# LPCB221_-_LIMIT_SWITCHES.net
KiCad netlist of a schematic drawn in Altium Designer
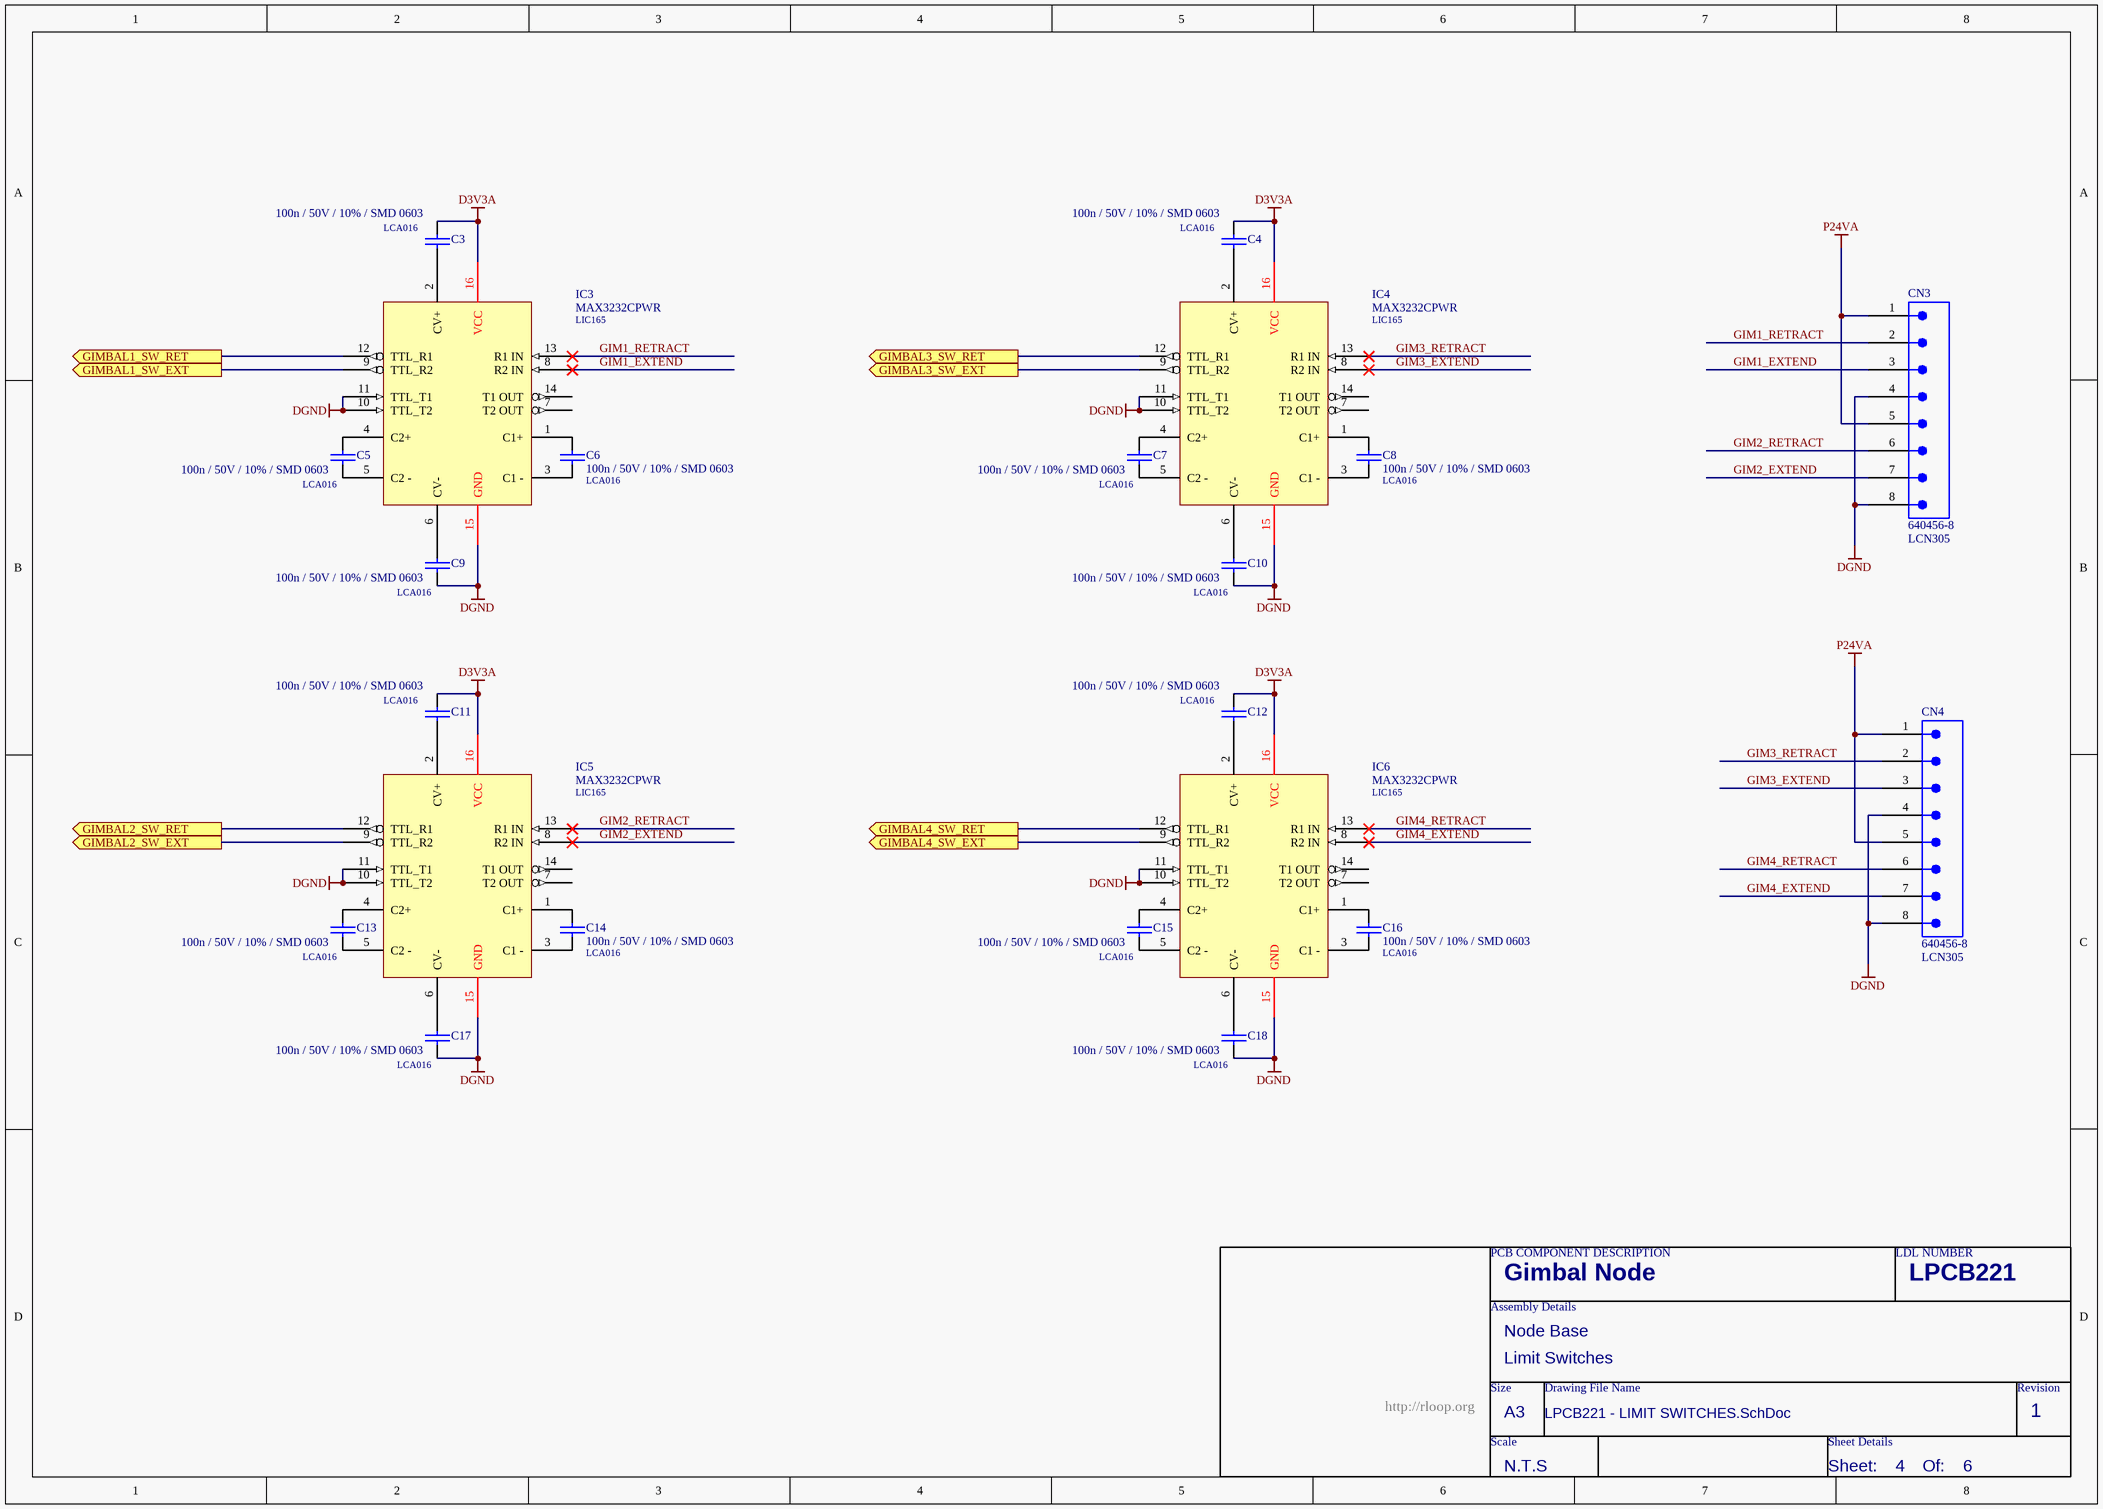
[diagram p0: LPCB221 - LIMIT SWITCHES.SchDoc]

(export (version "E")
  (design (tool "Eeschema 10.0.6"))
  (components
    (comp (ref "C3")
      (value "100n / 50V / 10% / SMD 0603")
      (footprint "LFP011__CC1608-0603-IPC7351_B")
      (description "Capacitor, Ceramic Chip, 100nF (0.1uF), 50V, 5%, SMD 0603 [LCA016]")
      (fields (field (name "LDL_NUMBER") "LCA016"))
      (libsource (lib "LDL_Capacitors") (part "100n / 50V / 10% / SMD 0603"))
    )
    (comp (ref "C4")
      (value "100n / 50V / 10% / SMD 0603")
      (footprint "LFP011__CC1608-0603-IPC7351_B")
      (description "Capacitor, Ceramic Chip, 100nF (0.1uF), 50V, 5%, SMD 0603 [LCA016]")
      (fields (field (name "LDL_NUMBER") "LCA016"))
      (libsource (lib "LDL_Capacitors") (part "100n / 50V / 10% / SMD 0603"))
    )
    (comp (ref "C5")
      (value "100n / 50V / 10% / SMD 0603")
      (footprint "LFP011__CC1608-0603-IPC7351_B")
      (description "Capacitor, Ceramic Chip, 100nF (0.1uF), 50V, 5%, SMD 0603 [LCA016]")
      (fields (field (name "LDL_NUMBER") "LCA016"))
      (libsource (lib "LDL_Capacitors") (part "100n / 50V / 10% / SMD 0603"))
    )
    (comp (ref "C6")
      (value "100n / 50V / 10% / SMD 0603")
      (footprint "LFP011__CC1608-0603-IPC7351_B")
      (description "Capacitor, Ceramic Chip, 100nF (0.1uF), 50V, 5%, SMD 0603 [LCA016]")
      (fields (field (name "LDL_NUMBER") "LCA016"))
      (libsource (lib "LDL_Capacitors") (part "100n / 50V / 10% / SMD 0603"))
    )
    (comp (ref "C7")
      (value "100n / 50V / 10% / SMD 0603")
      (footprint "LFP011__CC1608-0603-IPC7351_B")
      (description "Capacitor, Ceramic Chip, 100nF (0.1uF), 50V, 5%, SMD 0603 [LCA016]")
      (fields (field (name "LDL_NUMBER") "LCA016"))
      (libsource (lib "LDL_Capacitors") (part "100n / 50V / 10% / SMD 0603"))
    )
    (comp (ref "C8")
      (value "100n / 50V / 10% / SMD 0603")
      (footprint "LFP011__CC1608-0603-IPC7351_B")
      (description "Capacitor, Ceramic Chip, 100nF (0.1uF), 50V, 5%, SMD 0603 [LCA016]")
      (fields (field (name "LDL_NUMBER") "LCA016"))
      (libsource (lib "LDL_Capacitors") (part "100n / 50V / 10% / SMD 0603"))
    )
    (comp (ref "C9")
      (value "100n / 50V / 10% / SMD 0603")
      (footprint "LFP011__CC1608-0603-IPC7351_B")
      (description "Capacitor, Ceramic Chip, 100nF (0.1uF), 50V, 5%, SMD 0603 [LCA016]")
      (fields (field (name "LDL_NUMBER") "LCA016"))
      (libsource (lib "LDL_Capacitors") (part "100n / 50V / 10% / SMD 0603"))
    )
    (comp (ref "C10")
      (value "100n / 50V / 10% / SMD 0603")
      (footprint "LFP011__CC1608-0603-IPC7351_B")
      (description "Capacitor, Ceramic Chip, 100nF (0.1uF), 50V, 5%, SMD 0603 [LCA016]")
      (fields (field (name "LDL_NUMBER") "LCA016"))
      (libsource (lib "LDL_Capacitors") (part "100n / 50V / 10% / SMD 0603"))
    )
    (comp (ref "C11")
      (value "100n / 50V / 10% / SMD 0603")
      (footprint "LFP011__CC1608-0603-IPC7351_B")
      (description "Capacitor, Ceramic Chip, 100nF (0.1uF), 50V, 5%, SMD 0603 [LCA016]")
      (fields (field (name "LDL_NUMBER") "LCA016"))
      (libsource (lib "LDL_Capacitors") (part "100n / 50V / 10% / SMD 0603"))
    )
    (comp (ref "C12")
      (value "100n / 50V / 10% / SMD 0603")
      (footprint "LFP011__CC1608-0603-IPC7351_B")
      (description "Capacitor, Ceramic Chip, 100nF (0.1uF), 50V, 5%, SMD 0603 [LCA016]")
      (fields (field (name "LDL_NUMBER") "LCA016"))
      (libsource (lib "LDL_Capacitors") (part "100n / 50V / 10% / SMD 0603"))
    )
    (comp (ref "C13")
      (value "100n / 50V / 10% / SMD 0603")
      (footprint "LFP011__CC1608-0603-IPC7351_B")
      (description "Capacitor, Ceramic Chip, 100nF (0.1uF), 50V, 5%, SMD 0603 [LCA016]")
      (fields (field (name "LDL_NUMBER") "LCA016"))
      (libsource (lib "LDL_Capacitors") (part "100n / 50V / 10% / SMD 0603"))
    )
    (comp (ref "C14")
      (value "100n / 50V / 10% / SMD 0603")
      (footprint "LFP011__CC1608-0603-IPC7351_B")
      (description "Capacitor, Ceramic Chip, 100nF (0.1uF), 50V, 5%, SMD 0603 [LCA016]")
      (fields (field (name "LDL_NUMBER") "LCA016"))
      (libsource (lib "LDL_Capacitors") (part "100n / 50V / 10% / SMD 0603"))
    )
    (comp (ref "C15")
      (value "100n / 50V / 10% / SMD 0603")
      (footprint "LFP011__CC1608-0603-IPC7351_B")
      (description "Capacitor, Ceramic Chip, 100nF (0.1uF), 50V, 5%, SMD 0603 [LCA016]")
      (fields (field (name "LDL_NUMBER") "LCA016"))
      (libsource (lib "LDL_Capacitors") (part "100n / 50V / 10% / SMD 0603"))
    )
    (comp (ref "C16")
      (value "100n / 50V / 10% / SMD 0603")
      (footprint "LFP011__CC1608-0603-IPC7351_B")
      (description "Capacitor, Ceramic Chip, 100nF (0.1uF), 50V, 5%, SMD 0603 [LCA016]")
      (fields (field (name "LDL_NUMBER") "LCA016"))
      (libsource (lib "LDL_Capacitors") (part "100n / 50V / 10% / SMD 0603"))
    )
    (comp (ref "C17")
      (value "100n / 50V / 10% / SMD 0603")
      (footprint "LFP011__CC1608-0603-IPC7351_B")
      (description "Capacitor, Ceramic Chip, 100nF (0.1uF), 50V, 5%, SMD 0603 [LCA016]")
      (fields (field (name "LDL_NUMBER") "LCA016"))
      (libsource (lib "LDL_Capacitors") (part "100n / 50V / 10% / SMD 0603"))
    )
    (comp (ref "C18")
      (value "100n / 50V / 10% / SMD 0603")
      (footprint "LFP011__CC1608-0603-IPC7351_B")
      (description "Capacitor, Ceramic Chip, 100nF (0.1uF), 50V, 5%, SMD 0603 [LCA016]")
      (fields (field (name "LDL_NUMBER") "LCA016"))
      (libsource (lib "LDL_Capacitors") (part "100n / 50V / 10% / SMD 0603"))
    )
    (comp (ref "CN3")
      (value "640456-8")
      (footprint "640456-8")
      (description "Connector, Male Header, 8 Way")
      (fields (field (name "LDL_NUMBER") "LCN305"))
      (libsource (lib "LDL_Connectors") (part "640456-8"))
    )
    (comp (ref "CN4")
      (value "640456-8")
      (footprint "640456-8")
      (description "Connector, Male Header, 8 Way")
      (fields (field (name "LDL_NUMBER") "LCN305"))
      (libsource (lib "LDL_Connectors") (part "640456-8"))
    )
    (comp (ref "IC3")
      (value "MAX3232CPWR")
      (footprint "LFP049__TSSOP-16")
      (description "IC, RS232 Line Driver, 3.3V, SMD TSSOP16 [LIC165]")
      (fields (field (name "LDL_NUMBER") "LIC165"))
      (libsource (lib "LDL_Semiconductors") (part "MAX3232CPWR"))
    )
    (comp (ref "IC4")
      (value "MAX3232CPWR")
      (footprint "LFP049__TSSOP-16")
      (description "IC, RS232 Line Driver, 3.3V, SMD TSSOP16 [LIC165]")
      (fields (field (name "LDL_NUMBER") "LIC165"))
      (libsource (lib "LDL_Semiconductors") (part "MAX3232CPWR"))
    )
    (comp (ref "IC5")
      (value "MAX3232CPWR")
      (footprint "LFP049__TSSOP-16")
      (description "IC, RS232 Line Driver, 3.3V, SMD TSSOP16 [LIC165]")
      (fields (field (name "LDL_NUMBER") "LIC165"))
      (libsource (lib "LDL_Semiconductors") (part "MAX3232CPWR"))
    )
    (comp (ref "IC6")
      (value "MAX3232CPWR")
      (footprint "LFP049__TSSOP-16")
      (description "IC, RS232 Line Driver, 3.3V, SMD TSSOP16 [LIC165]")
      (fields (field (name "LDL_NUMBER") "LIC165"))
      (libsource (lib "LDL_Semiconductors") (part "MAX3232CPWR"))
    )
  )
  (nets
    (net (code "1") (name "/GIM1_EXTEND") (class "Default")
      (node (ref "CN3") (pin "3") (pinfunction "3_3") (pintype "passive"))
      (node (ref "IC3") (pin "8") (pinfunction "R2_IN_8") (pintype "input"))
    )
    (net (code "2") (name "/GIM1_RETRACT") (class "Default")
      (node (ref "CN3") (pin "2") (pinfunction "2_2") (pintype "passive"))
      (node (ref "IC3") (pin "13") (pinfunction "R1_IN_13") (pintype "input"))
    )
    (net (code "3") (name "/GIM2_EXTEND") (class "Default")
      (node (ref "CN3") (pin "7") (pinfunction "7_7") (pintype "passive"))
      (node (ref "IC5") (pin "8") (pinfunction "R2_IN_8") (pintype "input"))
    )
    (net (code "4") (name "/GIM2_RETRACT") (class "Default")
      (node (ref "CN3") (pin "6") (pinfunction "6_6") (pintype "passive"))
      (node (ref "IC5") (pin "13") (pinfunction "R1_IN_13") (pintype "input"))
    )
    (net (code "5") (name "/GIM3_EXTEND") (class "Default")
      (node (ref "CN4") (pin "3") (pinfunction "3_3") (pintype "passive"))
      (node (ref "IC4") (pin "8") (pinfunction "R2_IN_8") (pintype "input"))
    )
    (net (code "6") (name "/GIM3_RETRACT") (class "Default")
      (node (ref "CN4") (pin "2") (pinfunction "2_2") (pintype "passive"))
      (node (ref "IC4") (pin "13") (pinfunction "R1_IN_13") (pintype "input"))
    )
    (net (code "7") (name "/GIM4_EXTEND") (class "Default")
      (node (ref "CN4") (pin "7") (pinfunction "7_7") (pintype "passive"))
      (node (ref "IC6") (pin "8") (pinfunction "R2_IN_8") (pintype "input"))
    )
    (net (code "8") (name "/GIM4_RETRACT") (class "Default")
      (node (ref "CN4") (pin "6") (pinfunction "6_6") (pintype "passive"))
      (node (ref "IC6") (pin "13") (pinfunction "R1_IN_13") (pintype "input"))
    )
    (net (code "9") (name "/GIMBAL1_SW_EXT") (class "Default")
      (node (ref "IC3") (pin "9") (pinfunction "TTL_R2_9") (pintype "output"))
    )
    (net (code "10") (name "/GIMBAL1_SW_RET") (class "Default")
      (node (ref "IC3") (pin "12") (pinfunction "TTL_R1_12") (pintype "output"))
    )
    (net (code "11") (name "/GIMBAL2_SW_EXT") (class "Default")
      (node (ref "IC5") (pin "9") (pinfunction "TTL_R2_9") (pintype "output"))
    )
    (net (code "12") (name "/GIMBAL2_SW_RET") (class "Default")
      (node (ref "IC5") (pin "12") (pinfunction "TTL_R1_12") (pintype "output"))
    )
    (net (code "13") (name "/GIMBAL3_SW_EXT") (class "Default")
      (node (ref "IC4") (pin "9") (pinfunction "TTL_R2_9") (pintype "output"))
    )
    (net (code "14") (name "/GIMBAL3_SW_RET") (class "Default")
      (node (ref "IC4") (pin "12") (pinfunction "TTL_R1_12") (pintype "output"))
    )
    (net (code "15") (name "/GIMBAL4_SW_EXT") (class "Default")
      (node (ref "IC6") (pin "9") (pinfunction "TTL_R2_9") (pintype "output"))
    )
    (net (code "16") (name "/GIMBAL4_SW_RET") (class "Default")
      (node (ref "IC6") (pin "12") (pinfunction "TTL_R1_12") (pintype "output"))
    )
    (net (code "17") (name "D3V3A") (class "Default")
      (node (ref "C11") (pin "1") (pintype "passive"))
      (node (ref "C12") (pin "1") (pintype "passive"))
      (node (ref "C3") (pin "1") (pintype "passive"))
      (node (ref "C4") (pin "1") (pintype "passive"))
      (node (ref "IC3") (pin "16") (pinfunction "VCC_16") (pintype "power_in"))
      (node (ref "IC4") (pin "16") (pinfunction "VCC_16") (pintype "power_in"))
      (node (ref "IC5") (pin "16") (pinfunction "VCC_16") (pintype "power_in"))
      (node (ref "IC6") (pin "16") (pinfunction "VCC_16") (pintype "power_in"))
    )
    (net (code "18") (name "DGND") (class "Default")
      (node (ref "C10") (pin "2") (pintype "passive"))
      (node (ref "C17") (pin "2") (pintype "passive"))
      (node (ref "C18") (pin "2") (pintype "passive"))
      (node (ref "C9") (pin "2") (pintype "passive"))
      (node (ref "CN3") (pin "4") (pinfunction "4_4") (pintype "passive"))
      (node (ref "CN3") (pin "8") (pinfunction "8_8") (pintype "passive"))
      (node (ref "CN4") (pin "4") (pinfunction "4_4") (pintype "passive"))
      (node (ref "CN4") (pin "8") (pinfunction "8_8") (pintype "passive"))
      (node (ref "IC3") (pin "10") (pinfunction "TTL_T2_10") (pintype "input"))
      (node (ref "IC3") (pin "11") (pinfunction "TTL_T1_11") (pintype "input"))
      (node (ref "IC3") (pin "15") (pinfunction "GND_15") (pintype "power_in"))
      (node (ref "IC4") (pin "10") (pinfunction "TTL_T2_10") (pintype "input"))
      (node (ref "IC4") (pin "11") (pinfunction "TTL_T1_11") (pintype "input"))
      (node (ref "IC4") (pin "15") (pinfunction "GND_15") (pintype "power_in"))
      (node (ref "IC5") (pin "10") (pinfunction "TTL_T2_10") (pintype "input"))
      (node (ref "IC5") (pin "11") (pinfunction "TTL_T1_11") (pintype "input"))
      (node (ref "IC5") (pin "15") (pinfunction "GND_15") (pintype "power_in"))
      (node (ref "IC6") (pin "10") (pinfunction "TTL_T2_10") (pintype "input"))
      (node (ref "IC6") (pin "11") (pinfunction "TTL_T1_11") (pintype "input"))
      (node (ref "IC6") (pin "15") (pinfunction "GND_15") (pintype "power_in"))
    )
    (net (code "19") (name "Net-(IC3-C1+)") (class "Default")
      (node (ref "C6") (pin "1") (pintype "passive"))
      (node (ref "IC3") (pin "1") (pinfunction "C1+_1") (pintype "passive"))
    )
    (net (code "20") (name "Net-(IC3-C1_-)") (class "Default")
      (node (ref "C6") (pin "2") (pintype "passive"))
      (node (ref "IC3") (pin "3") (pinfunction "C1_-_3") (pintype "passive"))
    )
    (net (code "21") (name "Net-(IC3-C2+)") (class "Default")
      (node (ref "C5") (pin "1") (pintype "passive"))
      (node (ref "IC3") (pin "4") (pinfunction "C2+_4") (pintype "passive"))
    )
    (net (code "22") (name "Net-(IC3-C2_-)") (class "Default")
      (node (ref "C5") (pin "2") (pintype "passive"))
      (node (ref "IC3") (pin "5") (pinfunction "C2_-_5") (pintype "passive"))
    )
    (net (code "23") (name "Net-(IC3-CV+)") (class "Default")
      (node (ref "C3") (pin "2") (pintype "passive"))
      (node (ref "IC3") (pin "2") (pinfunction "CV+_2") (pintype "passive"))
    )
    (net (code "24") (name "Net-(IC3-CV-)") (class "Default")
      (node (ref "C9") (pin "1") (pintype "passive"))
      (node (ref "IC3") (pin "6") (pinfunction "CV-_6") (pintype "passive"))
    )
    (net (code "25") (name "Net-(IC4-C1+)") (class "Default")
      (node (ref "C8") (pin "1") (pintype "passive"))
      (node (ref "IC4") (pin "1") (pinfunction "C1+_1") (pintype "passive"))
    )
    (net (code "26") (name "Net-(IC4-C1_-)") (class "Default")
      (node (ref "C8") (pin "2") (pintype "passive"))
      (node (ref "IC4") (pin "3") (pinfunction "C1_-_3") (pintype "passive"))
    )
    (net (code "27") (name "Net-(IC4-C2+)") (class "Default")
      (node (ref "C7") (pin "1") (pintype "passive"))
      (node (ref "IC4") (pin "4") (pinfunction "C2+_4") (pintype "passive"))
    )
    (net (code "28") (name "Net-(IC4-C2_-)") (class "Default")
      (node (ref "C7") (pin "2") (pintype "passive"))
      (node (ref "IC4") (pin "5") (pinfunction "C2_-_5") (pintype "passive"))
    )
    (net (code "29") (name "Net-(IC4-CV+)") (class "Default")
      (node (ref "C4") (pin "2") (pintype "passive"))
      (node (ref "IC4") (pin "2") (pinfunction "CV+_2") (pintype "passive"))
    )
    (net (code "30") (name "Net-(IC4-CV-)") (class "Default")
      (node (ref "C10") (pin "1") (pintype "passive"))
      (node (ref "IC4") (pin "6") (pinfunction "CV-_6") (pintype "passive"))
    )
    (net (code "31") (name "Net-(IC5-C1+)") (class "Default")
      (node (ref "C14") (pin "1") (pintype "passive"))
      (node (ref "IC5") (pin "1") (pinfunction "C1+_1") (pintype "passive"))
    )
    (net (code "32") (name "Net-(IC5-C1_-)") (class "Default")
      (node (ref "C14") (pin "2") (pintype "passive"))
      (node (ref "IC5") (pin "3") (pinfunction "C1_-_3") (pintype "passive"))
    )
    (net (code "33") (name "Net-(IC5-C2+)") (class "Default")
      (node (ref "C13") (pin "1") (pintype "passive"))
      (node (ref "IC5") (pin "4") (pinfunction "C2+_4") (pintype "passive"))
    )
    (net (code "34") (name "Net-(IC5-C2_-)") (class "Default")
      (node (ref "C13") (pin "2") (pintype "passive"))
      (node (ref "IC5") (pin "5") (pinfunction "C2_-_5") (pintype "passive"))
    )
    (net (code "35") (name "Net-(IC5-CV+)") (class "Default")
      (node (ref "C11") (pin "2") (pintype "passive"))
      (node (ref "IC5") (pin "2") (pinfunction "CV+_2") (pintype "passive"))
    )
    (net (code "36") (name "Net-(IC5-CV-)") (class "Default")
      (node (ref "C17") (pin "1") (pintype "passive"))
      (node (ref "IC5") (pin "6") (pinfunction "CV-_6") (pintype "passive"))
    )
    (net (code "37") (name "Net-(IC6-C1+)") (class "Default")
      (node (ref "C16") (pin "1") (pintype "passive"))
      (node (ref "IC6") (pin "1") (pinfunction "C1+_1") (pintype "passive"))
    )
    (net (code "38") (name "Net-(IC6-C1_-)") (class "Default")
      (node (ref "C16") (pin "2") (pintype "passive"))
      (node (ref "IC6") (pin "3") (pinfunction "C1_-_3") (pintype "passive"))
    )
    (net (code "39") (name "Net-(IC6-C2+)") (class "Default")
      (node (ref "C15") (pin "1") (pintype "passive"))
      (node (ref "IC6") (pin "4") (pinfunction "C2+_4") (pintype "passive"))
    )
    (net (code "40") (name "Net-(IC6-C2_-)") (class "Default")
      (node (ref "C15") (pin "2") (pintype "passive"))
      (node (ref "IC6") (pin "5") (pinfunction "C2_-_5") (pintype "passive"))
    )
    (net (code "41") (name "Net-(IC6-CV+)") (class "Default")
      (node (ref "C12") (pin "2") (pintype "passive"))
      (node (ref "IC6") (pin "2") (pinfunction "CV+_2") (pintype "passive"))
    )
    (net (code "42") (name "Net-(IC6-CV-)") (class "Default")
      (node (ref "C18") (pin "1") (pintype "passive"))
      (node (ref "IC6") (pin "6") (pinfunction "CV-_6") (pintype "passive"))
    )
    (net (code "43") (name "P24VA") (class "Default")
      (node (ref "CN3") (pin "1") (pinfunction "1_1") (pintype "passive"))
      (node (ref "CN3") (pin "5") (pinfunction "5_5") (pintype "passive"))
      (node (ref "CN4") (pin "1") (pinfunction "1_1") (pintype "passive"))
      (node (ref "CN4") (pin "5") (pinfunction "5_5") (pintype "passive"))
    )
    (net (code "44") (name "unconnected-(IC3-T1_OUT-Pad14)") (class "Default")
      (node (ref "IC3") (pin "14") (pinfunction "T1_OUT_14") (pintype "output"))
    )
    (net (code "45") (name "unconnected-(IC3-T2_OUT-Pad7)") (class "Default")
      (node (ref "IC3") (pin "7") (pinfunction "T2_OUT_7") (pintype "output"))
    )
    (net (code "46") (name "unconnected-(IC4-T1_OUT-Pad14)") (class "Default")
      (node (ref "IC4") (pin "14") (pinfunction "T1_OUT_14") (pintype "output"))
    )
    (net (code "47") (name "unconnected-(IC4-T2_OUT-Pad7)") (class "Default")
      (node (ref "IC4") (pin "7") (pinfunction "T2_OUT_7") (pintype "output"))
    )
    (net (code "48") (name "unconnected-(IC5-T1_OUT-Pad14)") (class "Default")
      (node (ref "IC5") (pin "14") (pinfunction "T1_OUT_14") (pintype "output"))
    )
    (net (code "49") (name "unconnected-(IC5-T2_OUT-Pad7)") (class "Default")
      (node (ref "IC5") (pin "7") (pinfunction "T2_OUT_7") (pintype "output"))
    )
    (net (code "50") (name "unconnected-(IC6-T1_OUT-Pad14)") (class "Default")
      (node (ref "IC6") (pin "14") (pinfunction "T1_OUT_14") (pintype "output"))
    )
    (net (code "51") (name "unconnected-(IC6-T2_OUT-Pad7)") (class "Default")
      (node (ref "IC6") (pin "7") (pinfunction "T2_OUT_7") (pintype "output"))
    )
  )
)
